# driver_am26c31_isolated.net
KiCad netlist of a schematic drawn in Altium Designer
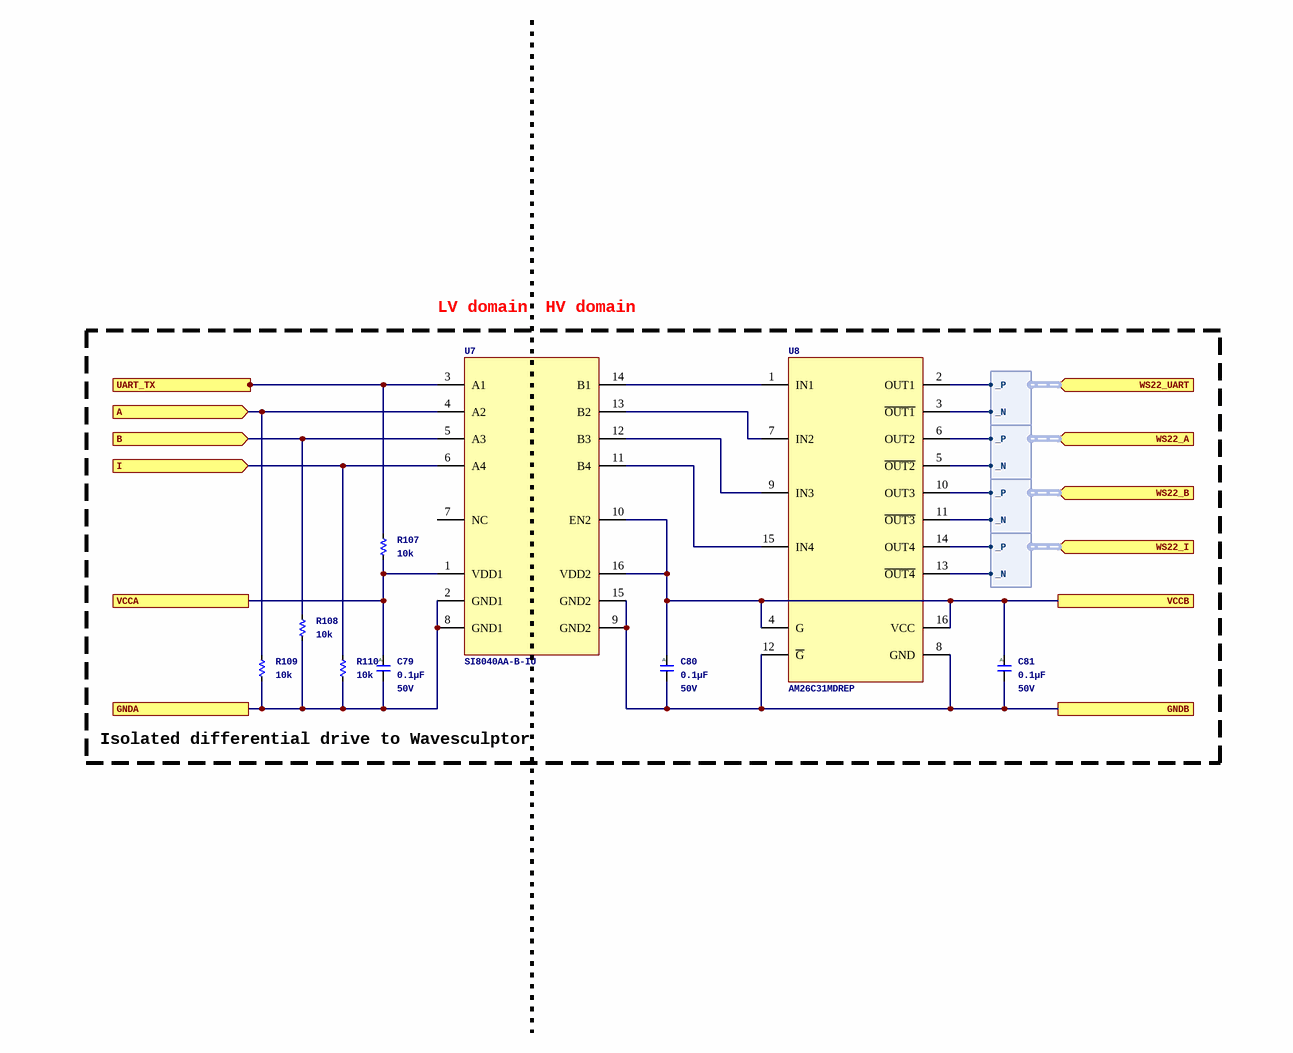
[diagram p0: driver_am26c31_isolated.SchDoc]

(export (version "E")
  (design (tool "Eeschema 10.0.6"))
  (components
    (comp (ref "C79")
      (value "CGA2B3X7R1H104M050BB")
      (footprint "C0402_0.55MM")
      (description "CAP CER 0.1UF 50V X7R 0402")
      (fields
        (field (name "CAPACITANCE") "0.1µF")
        (field (name "VOLTAGE - RATED") "50V")
        (field (name "TOLERANCE") "±20%")
        (field (name "MANUFACTURER") "TDK Corporation")
      )
      (libsource (lib "sscp") (part "__template_cap_auto"))
    )
    (comp (ref "C80")
      (value "CGA2B3X7R1H104M050BB")
      (footprint "C0402_0.55MM")
      (description "CAP CER 0.1UF 50V X7R 0402")
      (fields
        (field (name "CAPACITANCE") "0.1µF")
        (field (name "VOLTAGE - RATED") "50V")
        (field (name "TOLERANCE") "±20%")
        (field (name "MANUFACTURER") "TDK Corporation")
      )
      (libsource (lib "sscp") (part "__template_cap_auto"))
    )
    (comp (ref "C81")
      (value "CGA2B3X7R1H104M050BB")
      (footprint "C0402_0.55MM")
      (description "CAP CER 0.1UF 50V X7R 0402")
      (fields
        (field (name "CAPACITANCE") "0.1µF")
        (field (name "VOLTAGE - RATED") "50V")
        (field (name "TOLERANCE") "±20%")
        (field (name "MANUFACTURER") "TDK Corporation")
      )
      (libsource (lib "sscp") (part "__template_cap_auto"))
    )
    (comp (ref "R107")
      (value "ERJ-2RKF1002X")
      (footprint "R0402_0.40MM")
      (description "RES SMD 10K OHM 1% 1/10W 0402")
      (fields
        (field (name "RESISTANCE") "10k")
        (field (name "TOLERANCE") "±1%")
        (field (name "MANUFACTURER") "Panasonic Electronic Components")
      )
      (libsource (lib "sscp") (part "__template_resistor"))
    )
    (comp (ref "R108")
      (value "ERJ-2RKF1002X")
      (footprint "R0402_0.40MM")
      (description "RES SMD 10K OHM 1% 1/10W 0402")
      (fields
        (field (name "RESISTANCE") "10k")
        (field (name "TOLERANCE") "±1%")
        (field (name "MANUFACTURER") "Panasonic Electronic Components")
      )
      (libsource (lib "sscp") (part "__template_resistor"))
    )
    (comp (ref "R109")
      (value "ERJ-2RKF1002X")
      (footprint "R0402_0.40MM")
      (description "RES SMD 10K OHM 1% 1/10W 0402")
      (fields
        (field (name "RESISTANCE") "10k")
        (field (name "TOLERANCE") "±1%")
        (field (name "MANUFACTURER") "Panasonic Electronic Components")
      )
      (libsource (lib "sscp") (part "__template_resistor"))
    )
    (comp (ref "R110")
      (value "ERJ-2RKF1002X")
      (footprint "R0402_0.40MM")
      (description "RES SMD 10K OHM 1% 1/10W 0402")
      (fields
        (field (name "RESISTANCE") "10k")
        (field (name "TOLERANCE") "±1%")
        (field (name "MANUFACTURER") "Panasonic Electronic Components")
      )
      (libsource (lib "sscp") (part "__template_resistor"))
    )
    (comp (ref "U7")
      (value "SI8040AA-B-IU")
      (footprint "16SSOP635")
      (description "4 ch 1 kV digital isolator")
      (fields (field (name "MANUFACTURER") "Skyworks Solutions"))
      (libsource (lib "SSCP") (part "ISO_SI8040AA-B-IU"))
    )
    (comp (ref "U8")
      (value "AM26C31MDREP")
      (footprint "16SOIC150")
      (description "IC QUAD DIFF LINE DRIVER 16-SOIC")
      (fields (field (name "MANUFACTURER") "Texas Instruments"))
      (libsource (lib "SSCP") (part "RS422_AM26C31QDR"))
    )
  )
  (nets
    (net (code "3") (name "/A") (class "Default")
      (node (ref "R109") (pin "2") (pintype "passive"))
      (node (ref "U7") (pin "4") (pinfunction "A2_4") (pintype "passive"))
    )
    (net (code "4") (name "/B") (class "Default")
      (node (ref "R108") (pin "2") (pintype "passive"))
      (node (ref "U7") (pin "5") (pinfunction "A3_5") (pintype "passive"))
    )
    (net (code "5") (name "/GNDA") (class "Default")
      (node (ref "C79") (pin "2") (pintype "passive"))
      (node (ref "R108") (pin "1") (pintype "passive"))
      (node (ref "R109") (pin "1") (pintype "passive"))
      (node (ref "R110") (pin "1") (pintype "passive"))
      (node (ref "U7") (pin "2") (pinfunction "GND1_2") (pintype "passive"))
      (node (ref "U7") (pin "8") (pinfunction "GND1_8") (pintype "passive"))
    )
    (net (code "6") (name "/GNDB") (class "Default")
      (node (ref "C80") (pin "2") (pintype "passive"))
      (node (ref "C81") (pin "2") (pintype "passive"))
      (node (ref "U7") (pin "15") (pinfunction "GND2_15") (pintype "passive"))
      (node (ref "U7") (pin "9") (pinfunction "GND2_9") (pintype "passive"))
      (node (ref "U8") (pin "12") (pinfunction "~{G}_12") (pintype "passive"))
      (node (ref "U8") (pin "8") (pinfunction "GND_8") (pintype "passive"))
    )
    (net (code "7") (name "/I") (class "Default")
      (node (ref "R110") (pin "2") (pintype "passive"))
      (node (ref "U7") (pin "6") (pinfunction "A4_6") (pintype "passive"))
    )
    (net (code "8") (name "/UART_TX") (class "Default")
      (node (ref "R107") (pin "2") (pintype "passive"))
      (node (ref "U7") (pin "3") (pinfunction "A1_3") (pintype "passive"))
    )
    (net (code "9") (name "/VCCA") (class "Default")
      (node (ref "C79") (pin "1") (pintype "passive"))
      (node (ref "R107") (pin "1") (pintype "passive"))
      (node (ref "U7") (pin "1") (pinfunction "VDD1_1") (pintype "passive"))
    )
    (net (code "10") (name "/VCCB") (class "Default")
      (node (ref "C80") (pin "1") (pintype "passive"))
      (node (ref "C81") (pin "1") (pintype "passive"))
      (node (ref "U7") (pin "10") (pinfunction "EN2_10") (pintype "passive"))
      (node (ref "U7") (pin "16") (pinfunction "VDD2_16") (pintype "passive"))
      (node (ref "U8") (pin "16") (pinfunction "VCC_16") (pintype "passive"))
      (node (ref "U8") (pin "4") (pinfunction "G_4") (pintype "passive"))
    )
    (net (code "13") (name "Net-(U7-B1)") (class "Default")
      (node (ref "U7") (pin "14") (pinfunction "B1_14") (pintype "passive"))
      (node (ref "U8") (pin "1") (pinfunction "IN1_1") (pintype "passive"))
    )
    (net (code "14") (name "Net-(U7-B2)") (class "Default")
      (node (ref "U7") (pin "13") (pinfunction "B2_13") (pintype "passive"))
      (node (ref "U8") (pin "7") (pinfunction "IN2_7") (pintype "passive"))
    )
    (net (code "15") (name "Net-(U7-B3)") (class "Default")
      (node (ref "U7") (pin "12") (pinfunction "B3_12") (pintype "passive"))
      (node (ref "U8") (pin "9") (pinfunction "IN3_9") (pintype "passive"))
    )
    (net (code "16") (name "Net-(U7-B4)") (class "Default")
      (node (ref "U7") (pin "11") (pinfunction "B4_11") (pintype "passive"))
      (node (ref "U8") (pin "15") (pinfunction "IN4_15") (pintype "passive"))
    )
    (net (code "17") (name "unconnected-(U7-NC-Pad7)") (class "Default")
      (node (ref "U7") (pin "7") (pinfunction "NC_7") (pintype "passive"))
    )
    (net (code "18") (name "unconnected-(U8-OUT1-Pad2)") (class "Default")
      (node (ref "U8") (pin "2") (pinfunction "OUT1_2") (pintype "passive"))
    )
    (net (code "19") (name "unconnected-(U8-OUT2-Pad6)") (class "Default")
      (node (ref "U8") (pin "6") (pinfunction "OUT2_6") (pintype "passive"))
    )
    (net (code "20") (name "unconnected-(U8-OUT3-Pad10)") (class "Default")
      (node (ref "U8") (pin "10") (pinfunction "OUT3_10") (pintype "passive"))
    )
    (net (code "21") (name "unconnected-(U8-OUT4-Pad14)") (class "Default")
      (node (ref "U8") (pin "14") (pinfunction "OUT4_14") (pintype "passive"))
    )
    (net (code "22") (name "unconnected-(U8-~{OUT1}-Pad3)") (class "Default")
      (node (ref "U8") (pin "3") (pinfunction "~{OUT1}_3") (pintype "passive"))
    )
    (net (code "23") (name "unconnected-(U8-~{OUT2}-Pad5)") (class "Default")
      (node (ref "U8") (pin "5") (pinfunction "~{OUT2}_5") (pintype "passive"))
    )
    (net (code "24") (name "unconnected-(U8-~{OUT3}-Pad11)") (class "Default")
      (node (ref "U8") (pin "11") (pinfunction "~{OUT3}_11") (pintype "passive"))
    )
    (net (code "25") (name "unconnected-(U8-~{OUT4}-Pad13)") (class "Default")
      (node (ref "U8") (pin "13") (pinfunction "~{OUT4}_13") (pintype "passive"))
    )
  )
)
